# 2_Unextended_Standard_matrix.net
KiCad netlist of a schematic drawn in Altium Designer
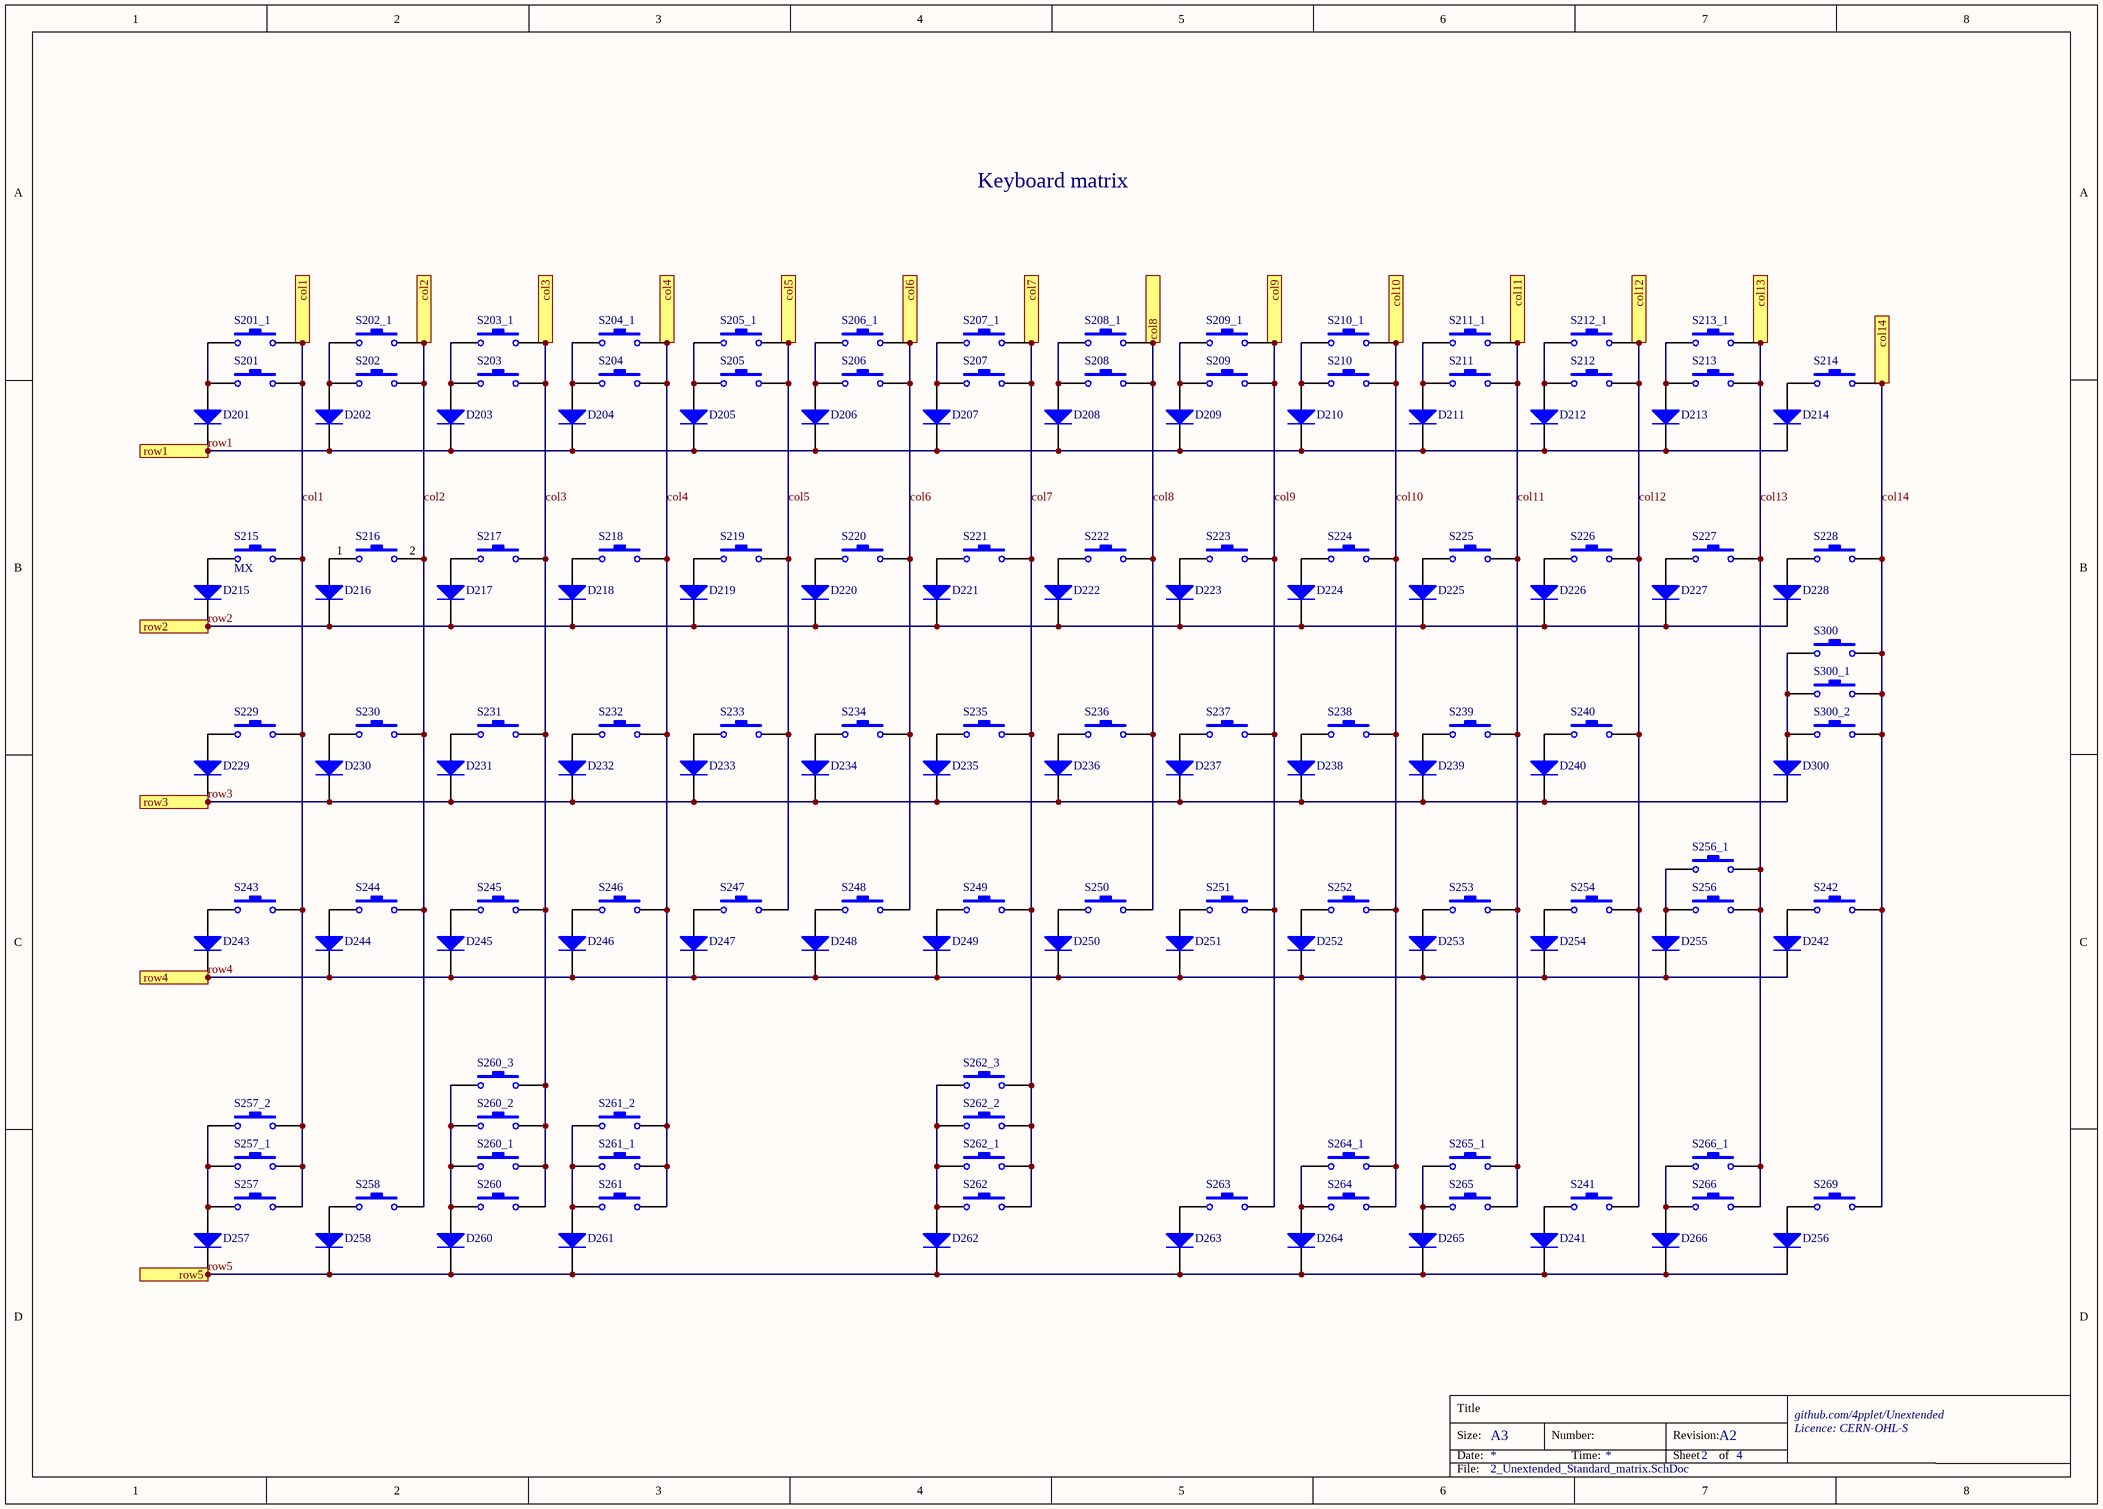
[diagram p0: 2_Unextended_Standard_matrix.SchDoc]

(export (version "E")
  (design (tool "Eeschema 10.0.6"))
  (components
    (comp (ref "D201")
      (value "Diode")
      (footprint "SOD-123")
      (description "Default Diode")
      (fields (field (name "LCSC PART #") "C81598") (field (name "MRF.PART") "1N4148W"))
      (libsource (lib "Miscellaneous Devices") (part "Diode"))
    )
    (comp (ref "D202")
      (value "Diode")
      (footprint "SOD-123")
      (description "Default Diode")
      (fields (field (name "LCSC PART #") "C81598") (field (name "MRF.PART") "1N4148W"))
      (libsource (lib "Miscellaneous Devices") (part "Diode"))
    )
    (comp (ref "D203")
      (value "Diode")
      (footprint "SOD-123")
      (description "Default Diode")
      (fields (field (name "LCSC PART #") "C81598") (field (name "MRF.PART") "1N4148W"))
      (libsource (lib "Miscellaneous Devices") (part "Diode"))
    )
    (comp (ref "D204")
      (value "Diode")
      (footprint "SOD-123")
      (description "Default Diode")
      (fields (field (name "LCSC PART #") "C81598") (field (name "MRF.PART") "1N4148W"))
      (libsource (lib "Miscellaneous Devices") (part "Diode"))
    )
    (comp (ref "D205")
      (value "Diode")
      (footprint "SOD-123")
      (description "Default Diode")
      (fields (field (name "LCSC PART #") "C81598") (field (name "MRF.PART") "1N4148W"))
      (libsource (lib "Miscellaneous Devices") (part "Diode"))
    )
    (comp (ref "D206")
      (value "Diode")
      (footprint "SOD-123")
      (description "Default Diode")
      (fields (field (name "LCSC PART #") "C81598") (field (name "MRF.PART") "1N4148W"))
      (libsource (lib "Miscellaneous Devices") (part "Diode"))
    )
    (comp (ref "D207")
      (value "Diode")
      (footprint "SOD-123")
      (description "Default Diode")
      (fields (field (name "LCSC PART #") "C81598") (field (name "MRF.PART") "1N4148W"))
      (libsource (lib "Miscellaneous Devices") (part "Diode"))
    )
    (comp (ref "D208")
      (value "Diode")
      (footprint "SOD-123")
      (description "Default Diode")
      (fields (field (name "LCSC PART #") "C81598") (field (name "MRF.PART") "1N4148W"))
      (libsource (lib "Miscellaneous Devices") (part "Diode"))
    )
    (comp (ref "D209")
      (value "Diode")
      (footprint "SOD-123")
      (description "Default Diode")
      (fields (field (name "LCSC PART #") "C81598") (field (name "MRF.PART") "1N4148W"))
      (libsource (lib "Miscellaneous Devices") (part "Diode"))
    )
    (comp (ref "D210")
      (value "Diode")
      (footprint "SOD-123")
      (description "Default Diode")
      (fields (field (name "LCSC PART #") "C81598") (field (name "MRF.PART") "1N4148W"))
      (libsource (lib "Miscellaneous Devices") (part "Diode"))
    )
    (comp (ref "D211")
      (value "Diode")
      (footprint "SOD-123")
      (description "Default Diode")
      (fields (field (name "LCSC PART #") "C81598") (field (name "MRF.PART") "1N4148W"))
      (libsource (lib "Miscellaneous Devices") (part "Diode"))
    )
    (comp (ref "D212")
      (value "Diode")
      (footprint "SOD-123")
      (description "Default Diode")
      (fields (field (name "LCSC PART #") "C81598") (field (name "MRF.PART") "1N4148W"))
      (libsource (lib "Miscellaneous Devices") (part "Diode"))
    )
    (comp (ref "D213")
      (value "Diode")
      (footprint "SOD-123")
      (description "Default Diode")
      (fields (field (name "LCSC PART #") "C81598") (field (name "MRF.PART") "1N4148W"))
      (libsource (lib "Miscellaneous Devices") (part "Diode"))
    )
    (comp (ref "D214")
      (value "Diode")
      (footprint "SOD-123")
      (description "Default Diode")
      (fields (field (name "LCSC PART #") "C81598") (field (name "MRF.PART") "1N4148W"))
      (libsource (lib "Miscellaneous Devices") (part "Diode"))
    )
    (comp (ref "D215")
      (value "Diode")
      (footprint "SOD-123")
      (description "Default Diode")
      (fields (field (name "LCSC PART #") "C81598") (field (name "MRF.PART") "1N4148W"))
      (libsource (lib "Miscellaneous Devices") (part "Diode"))
    )
    (comp (ref "D216")
      (value "Diode")
      (footprint "SOD-123")
      (description "Default Diode")
      (fields (field (name "LCSC PART #") "C81598") (field (name "MRF.PART") "1N4148W"))
      (libsource (lib "Miscellaneous Devices") (part "Diode"))
    )
    (comp (ref "D217")
      (value "Diode")
      (footprint "SOD-123")
      (description "Default Diode")
      (fields (field (name "LCSC PART #") "C81598") (field (name "MRF.PART") "1N4148W"))
      (libsource (lib "Miscellaneous Devices") (part "Diode"))
    )
    (comp (ref "D218")
      (value "Diode")
      (footprint "SOD-123")
      (description "Default Diode")
      (fields (field (name "LCSC PART #") "C81598") (field (name "MRF.PART") "1N4148W"))
      (libsource (lib "Miscellaneous Devices") (part "Diode"))
    )
    (comp (ref "D219")
      (value "Diode")
      (footprint "SOD-123")
      (description "Default Diode")
      (fields (field (name "LCSC PART #") "C81598") (field (name "MRF.PART") "1N4148W"))
      (libsource (lib "Miscellaneous Devices") (part "Diode"))
    )
    (comp (ref "D220")
      (value "Diode")
      (footprint "SOD-123")
      (description "Default Diode")
      (fields (field (name "LCSC PART #") "C81598") (field (name "MRF.PART") "1N4148W"))
      (libsource (lib "Miscellaneous Devices") (part "Diode"))
    )
    (comp (ref "D221")
      (value "Diode")
      (footprint "SOD-123")
      (description "Default Diode")
      (fields (field (name "LCSC PART #") "C81598") (field (name "MRF.PART") "1N4148W"))
      (libsource (lib "Miscellaneous Devices") (part "Diode"))
    )
    (comp (ref "D222")
      (value "Diode")
      (footprint "SOD-123")
      (description "Default Diode")
      (fields (field (name "LCSC PART #") "C81598") (field (name "MRF.PART") "1N4148W"))
      (libsource (lib "Miscellaneous Devices") (part "Diode"))
    )
    (comp (ref "D223")
      (value "Diode")
      (footprint "SOD-123")
      (description "Default Diode")
      (fields (field (name "LCSC PART #") "C81598") (field (name "MRF.PART") "1N4148W"))
      (libsource (lib "Miscellaneous Devices") (part "Diode"))
    )
    (comp (ref "D224")
      (value "Diode")
      (footprint "SOD-123")
      (description "Default Diode")
      (fields (field (name "LCSC PART #") "C81598") (field (name "MRF.PART") "1N4148W"))
      (libsource (lib "Miscellaneous Devices") (part "Diode"))
    )
    (comp (ref "D225")
      (value "Diode")
      (footprint "SOD-123")
      (description "Default Diode")
      (fields (field (name "LCSC PART #") "C81598") (field (name "MRF.PART") "1N4148W"))
      (libsource (lib "Miscellaneous Devices") (part "Diode"))
    )
    (comp (ref "D226")
      (value "Diode")
      (footprint "SOD-123")
      (description "Default Diode")
      (fields (field (name "LCSC PART #") "C81598") (field (name "MRF.PART") "1N4148W"))
      (libsource (lib "Miscellaneous Devices") (part "Diode"))
    )
    (comp (ref "D227")
      (value "Diode")
      (footprint "SOD-123")
      (description "Default Diode")
      (fields (field (name "LCSC PART #") "C81598") (field (name "MRF.PART") "1N4148W"))
      (libsource (lib "Miscellaneous Devices") (part "Diode"))
    )
    (comp (ref "D228")
      (value "Diode")
      (footprint "SOD-123")
      (description "Default Diode")
      (fields (field (name "LCSC PART #") "C81598") (field (name "MRF.PART") "1N4148W"))
      (libsource (lib "Miscellaneous Devices") (part "Diode"))
    )
    (comp (ref "D229")
      (value "Diode")
      (footprint "SOD-123")
      (description "Default Diode")
      (fields (field (name "LCSC PART #") "C81598") (field (name "MRF.PART") "1N4148W"))
      (libsource (lib "Miscellaneous Devices") (part "Diode"))
    )
    (comp (ref "D230")
      (value "Diode")
      (footprint "SOD-123")
      (description "Default Diode")
      (fields (field (name "LCSC PART #") "C81598") (field (name "MRF.PART") "1N4148W"))
      (libsource (lib "Miscellaneous Devices") (part "Diode"))
    )
    (comp (ref "D231")
      (value "Diode")
      (footprint "SOD-123")
      (description "Default Diode")
      (fields (field (name "LCSC PART #") "C81598") (field (name "MRF.PART") "1N4148W"))
      (libsource (lib "Miscellaneous Devices") (part "Diode"))
    )
    (comp (ref "D232")
      (value "Diode")
      (footprint "SOD-123")
      (description "Default Diode")
      (fields (field (name "LCSC PART #") "C81598") (field (name "MRF.PART") "1N4148W"))
      (libsource (lib "Miscellaneous Devices") (part "Diode"))
    )
    (comp (ref "D233")
      (value "Diode")
      (footprint "SOD-123")
      (description "Default Diode")
      (fields (field (name "LCSC PART #") "C81598") (field (name "MRF.PART") "1N4148W"))
      (libsource (lib "Miscellaneous Devices") (part "Diode"))
    )
    (comp (ref "D234")
      (value "Diode")
      (footprint "SOD-123")
      (description "Default Diode")
      (fields (field (name "LCSC PART #") "C81598") (field (name "MRF.PART") "1N4148W"))
      (libsource (lib "Miscellaneous Devices") (part "Diode"))
    )
    (comp (ref "D235")
      (value "Diode")
      (footprint "SOD-123")
      (description "Default Diode")
      (fields (field (name "LCSC PART #") "C81598") (field (name "MRF.PART") "1N4148W"))
      (libsource (lib "Miscellaneous Devices") (part "Diode"))
    )
    (comp (ref "D236")
      (value "Diode")
      (footprint "SOD-123")
      (description "Default Diode")
      (fields (field (name "LCSC PART #") "C81598") (field (name "MRF.PART") "1N4148W"))
      (libsource (lib "Miscellaneous Devices") (part "Diode"))
    )
    (comp (ref "D237")
      (value "Diode")
      (footprint "SOD-123")
      (description "Default Diode")
      (fields (field (name "LCSC PART #") "C81598") (field (name "MRF.PART") "1N4148W"))
      (libsource (lib "Miscellaneous Devices") (part "Diode"))
    )
    (comp (ref "D238")
      (value "Diode")
      (footprint "SOD-123")
      (description "Default Diode")
      (fields (field (name "LCSC PART #") "C81598") (field (name "MRF.PART") "1N4148W"))
      (libsource (lib "Miscellaneous Devices") (part "Diode"))
    )
    (comp (ref "D239")
      (value "Diode")
      (footprint "SOD-123")
      (description "Default Diode")
      (fields (field (name "LCSC PART #") "C81598") (field (name "MRF.PART") "1N4148W"))
      (libsource (lib "Miscellaneous Devices") (part "Diode"))
    )
    (comp (ref "D240")
      (value "Diode")
      (footprint "SOD-123")
      (description "Default Diode")
      (fields (field (name "LCSC PART #") "C81598") (field (name "MRF.PART") "1N4148W"))
      (libsource (lib "Miscellaneous Devices") (part "Diode"))
    )
    (comp (ref "D241")
      (value "Diode")
      (footprint "SOD-123")
      (description "Default Diode")
      (fields (field (name "LCSC PART #") "C81598") (field (name "MRF.PART") "1N4148W"))
      (libsource (lib "Miscellaneous Devices") (part "Diode"))
    )
    (comp (ref "D242")
      (value "Diode")
      (footprint "SOD-123")
      (description "Default Diode")
      (fields (field (name "LCSC PART #") "C81598") (field (name "MRF.PART") "1N4148W"))
      (libsource (lib "Miscellaneous Devices") (part "Diode"))
    )
    (comp (ref "D243")
      (value "Diode")
      (footprint "SOD-123")
      (description "Default Diode")
      (fields (field (name "LCSC PART #") "C81598") (field (name "MRF.PART") "1N4148W"))
      (libsource (lib "Miscellaneous Devices") (part "Diode"))
    )
    (comp (ref "D244")
      (value "Diode")
      (footprint "SOD-123")
      (description "Default Diode")
      (fields (field (name "LCSC PART #") "C81598") (field (name "MRF.PART") "1N4148W"))
      (libsource (lib "Miscellaneous Devices") (part "Diode"))
    )
    (comp (ref "D245")
      (value "Diode")
      (footprint "SOD-123")
      (description "Default Diode")
      (fields (field (name "LCSC PART #") "C81598") (field (name "MRF.PART") "1N4148W"))
      (libsource (lib "Miscellaneous Devices") (part "Diode"))
    )
    (comp (ref "D246")
      (value "Diode")
      (footprint "SOD-123")
      (description "Default Diode")
      (fields (field (name "LCSC PART #") "C81598") (field (name "MRF.PART") "1N4148W"))
      (libsource (lib "Miscellaneous Devices") (part "Diode"))
    )
    (comp (ref "D247")
      (value "Diode")
      (footprint "SOD-123")
      (description "Default Diode")
      (fields (field (name "LCSC PART #") "C81598") (field (name "MRF.PART") "1N4148W"))
      (libsource (lib "Miscellaneous Devices") (part "Diode"))
    )
    (comp (ref "D248")
      (value "Diode")
      (footprint "SOD-123")
      (description "Default Diode")
      (fields (field (name "LCSC PART #") "C81598") (field (name "MRF.PART") "1N4148W"))
      (libsource (lib "Miscellaneous Devices") (part "Diode"))
    )
    (comp (ref "D249")
      (value "Diode")
      (footprint "SOD-123")
      (description "Default Diode")
      (fields (field (name "LCSC PART #") "C81598") (field (name "MRF.PART") "1N4148W"))
      (libsource (lib "Miscellaneous Devices") (part "Diode"))
    )
    (comp (ref "D250")
      (value "Diode")
      (footprint "SOD-123")
      (description "Default Diode")
      (fields (field (name "LCSC PART #") "C81598") (field (name "MRF.PART") "1N4148W"))
      (libsource (lib "Miscellaneous Devices") (part "Diode"))
    )
    (comp (ref "D251")
      (value "Diode")
      (footprint "SOD-123")
      (description "Default Diode")
      (fields (field (name "LCSC PART #") "C81598") (field (name "MRF.PART") "1N4148W"))
      (libsource (lib "Miscellaneous Devices") (part "Diode"))
    )
    (comp (ref "D252")
      (value "Diode")
      (footprint "SOD-123")
      (description "Default Diode")
      (fields (field (name "LCSC PART #") "C81598") (field (name "MRF.PART") "1N4148W"))
      (libsource (lib "Miscellaneous Devices") (part "Diode"))
    )
    (comp (ref "D253")
      (value "Diode")
      (footprint "SOD-123")
      (description "Default Diode")
      (fields (field (name "LCSC PART #") "C81598") (field (name "MRF.PART") "1N4148W"))
      (libsource (lib "Miscellaneous Devices") (part "Diode"))
    )
    (comp (ref "D254")
      (value "Diode")
      (footprint "SOD-123")
      (description "Default Diode")
      (fields (field (name "LCSC PART #") "C81598") (field (name "MRF.PART") "1N4148W"))
      (libsource (lib "Miscellaneous Devices") (part "Diode"))
    )
    (comp (ref "D255")
      (value "Diode")
      (footprint "SOD-123")
      (description "Default Diode")
      (fields (field (name "LCSC PART #") "C81598") (field (name "MRF.PART") "1N4148W"))
      (libsource (lib "Miscellaneous Devices") (part "Diode"))
    )
    (comp (ref "D256")
      (value "Diode")
      (footprint "SOD-123")
      (description "Default Diode")
      (fields (field (name "LCSC PART #") "C81598") (field (name "MRF.PART") "1N4148W"))
      (libsource (lib "Miscellaneous Devices") (part "Diode"))
    )
    (comp (ref "D257")
      (value "Diode")
      (footprint "SOD-123")
      (description "Default Diode")
      (fields (field (name "LCSC PART #") "C81598") (field (name "MRF.PART") "1N4148W"))
      (libsource (lib "Miscellaneous Devices") (part "Diode"))
    )
    (comp (ref "D258")
      (value "Diode")
      (footprint "SOD-123")
      (description "Default Diode")
      (fields (field (name "LCSC PART #") "C81598") (field (name "MRF.PART") "1N4148W"))
      (libsource (lib "Miscellaneous Devices") (part "Diode"))
    )
    (comp (ref "D260")
      (value "Diode")
      (footprint "SOD-123")
      (description "Default Diode")
      (fields (field (name "LCSC PART #") "C81598") (field (name "MRF.PART") "1N4148W"))
      (libsource (lib "Miscellaneous Devices") (part "Diode"))
    )
    (comp (ref "D261")
      (value "Diode")
      (footprint "SOD-123")
      (description "Default Diode")
      (fields (field (name "LCSC PART #") "C81598") (field (name "MRF.PART") "1N4148W"))
      (libsource (lib "Miscellaneous Devices") (part "Diode"))
    )
    (comp (ref "D262")
      (value "Diode")
      (footprint "SOD-123")
      (description "Default Diode")
      (fields (field (name "LCSC PART #") "C81598") (field (name "MRF.PART") "1N4148W"))
      (libsource (lib "Miscellaneous Devices") (part "Diode"))
    )
    (comp (ref "D263")
      (value "Diode")
      (footprint "SOD-123")
      (description "Default Diode")
      (fields (field (name "LCSC PART #") "C81598") (field (name "MRF.PART") "1N4148W"))
      (libsource (lib "Miscellaneous Devices") (part "Diode"))
    )
    (comp (ref "D264")
      (value "Diode")
      (footprint "SOD-123")
      (description "Default Diode")
      (fields (field (name "LCSC PART #") "C81598") (field (name "MRF.PART") "1N4148W"))
      (libsource (lib "Miscellaneous Devices") (part "Diode"))
    )
    (comp (ref "D265")
      (value "Diode")
      (footprint "SOD-123")
      (description "Default Diode")
      (fields (field (name "LCSC PART #") "C81598") (field (name "MRF.PART") "1N4148W"))
      (libsource (lib "Miscellaneous Devices") (part "Diode"))
    )
    (comp (ref "D266")
      (value "Diode")
      (footprint "SOD-123")
      (description "Default Diode")
      (fields (field (name "LCSC PART #") "C81598") (field (name "MRF.PART") "1N4148W"))
      (libsource (lib "Miscellaneous Devices") (part "Diode"))
    )
    (comp (ref "D300")
      (value "Diode")
      (footprint "SOD-123")
      (description "Default Diode")
      (fields (field (name "LCSC PART #") "C81598") (field (name "MRF.PART") "1N4148W"))
      (libsource (lib "Miscellaneous Devices") (part "Diode"))
    )
    (comp (ref "S201")
      (value "ALPS")
      (footprint "Alps-switch - switched pol")
      (description "Switch")
      (libsource (lib "Miscellaneous Devices") (part "SW-PB"))
    )
    (comp (ref "S201_1")
      (value "ALPS")
      (footprint "Alps-switch")
      (description "Switch")
      (libsource (lib "Miscellaneous Devices") (part "SW-PB"))
    )
    (comp (ref "S202")
      (value "ALPS")
      (footprint "Alps-switch - switched pol")
      (description "Switch")
      (libsource (lib "Miscellaneous Devices") (part "SW-PB"))
    )
    (comp (ref "S202_1")
      (value "ALPS")
      (footprint "Alps-switch")
      (description "Switch")
      (libsource (lib "Miscellaneous Devices") (part "SW-PB"))
    )
    (comp (ref "S203")
      (value "ALPS")
      (footprint "Alps-switch - switched pol")
      (description "Switch")
      (libsource (lib "Miscellaneous Devices") (part "SW-PB"))
    )
    (comp (ref "S203_1")
      (value "ALPS")
      (footprint "Alps-switch")
      (description "Switch")
      (libsource (lib "Miscellaneous Devices") (part "SW-PB"))
    )
    (comp (ref "S204")
      (value "ALPS")
      (footprint "Alps-switch - switched pol")
      (description "Switch")
      (libsource (lib "Miscellaneous Devices") (part "SW-PB"))
    )
    (comp (ref "S204_1")
      (value "ALPS")
      (footprint "Alps-switch")
      (description "Switch")
      (libsource (lib "Miscellaneous Devices") (part "SW-PB"))
    )
    (comp (ref "S205")
      (value "ALPS")
      (footprint "Alps-switch - switched pol")
      (description "Switch")
      (libsource (lib "Miscellaneous Devices") (part "SW-PB"))
    )
    (comp (ref "S205_1")
      (value "ALPS")
      (footprint "Alps-switch")
      (description "Switch")
      (libsource (lib "Miscellaneous Devices") (part "SW-PB"))
    )
    (comp (ref "S206")
      (value "ALPS")
      (footprint "Alps-switch - switched pol")
      (description "Switch")
      (libsource (lib "Miscellaneous Devices") (part "SW-PB"))
    )
    (comp (ref "S206_1")
      (value "ALPS")
      (footprint "Alps-switch")
      (description "Switch")
      (libsource (lib "Miscellaneous Devices") (part "SW-PB"))
    )
    (comp (ref "S207")
      (value "ALPS")
      (footprint "Alps-switch - switched pol")
      (description "Switch")
      (libsource (lib "Miscellaneous Devices") (part "SW-PB"))
    )
    (comp (ref "S207_1")
      (value "ALPS")
      (footprint "Alps-switch")
      (description "Switch")
      (libsource (lib "Miscellaneous Devices") (part "SW-PB"))
    )
    (comp (ref "S208")
      (value "ALPS")
      (footprint "Alps-switch - switched pol")
      (description "Switch")
      (libsource (lib "Miscellaneous Devices") (part "SW-PB"))
    )
    (comp (ref "S208_1")
      (value "ALPS")
      (footprint "Alps-switch")
      (description "Switch")
      (libsource (lib "Miscellaneous Devices") (part "SW-PB"))
    )
    (comp (ref "S209")
      (value "ALPS")
      (footprint "Alps-switch - switched pol")
      (description "Switch")
      (libsource (lib "Miscellaneous Devices") (part "SW-PB"))
    )
    (comp (ref "S209_1")
      (value "ALPS")
      (footprint "Alps-switch")
      (description "Switch")
      (libsource (lib "Miscellaneous Devices") (part "SW-PB"))
    )
    (comp (ref "S210")
      (value "ALPS")
      (footprint "Alps-switch - switched pol")
      (description "Switch")
      (libsource (lib "Miscellaneous Devices") (part "SW-PB"))
    )
    (comp (ref "S210_1")
      (value "ALPS")
      (footprint "Alps-switch")
      (description "Switch")
      (libsource (lib "Miscellaneous Devices") (part "SW-PB"))
    )
    (comp (ref "S211")
      (value "ALPS")
      (footprint "Alps-switch - switched pol")
      (description "Switch")
      (libsource (lib "Miscellaneous Devices") (part "SW-PB"))
    )
    (comp (ref "S211_1")
      (value "ALPS")
      (footprint "Alps-switch")
      (description "Switch")
      (libsource (lib "Miscellaneous Devices") (part "SW-PB"))
    )
    (comp (ref "S212")
      (value "ALPS")
      (footprint "Alps-switch - switched pol")
      (description "Switch")
      (libsource (lib "Miscellaneous Devices") (part "SW-PB"))
    )
    (comp (ref "S212_1")
      (value "ALPS")
      (footprint "Alps-switch")
      (description "Switch")
      (libsource (lib "Miscellaneous Devices") (part "SW-PB"))
    )
    (comp (ref "S213")
      (value "ALPS")
      (footprint "Alps-switch - switched pol")
      (description "Switch")
      (libsource (lib "Miscellaneous Devices") (part "SW-PB"))
    )
    (comp (ref "S213_1")
      (value "ALPS")
      (footprint "Alps-switch")
      (description "Switch")
      (libsource (lib "Miscellaneous Devices") (part "SW-PB"))
    )
    (comp (ref "S214")
      (value "ALPS")
      (footprint "ALPS-switch - 1.5U")
      (description "Switch")
      (libsource (lib "Miscellaneous Devices") (part "SW-PB"))
    )
    (comp (ref "S215")
      (value "MX")
      (footprint "Alps-switch - switched pol")
      (description "TAB")
      (libsource (lib "Miscellaneous Devices") (part "SW-PB"))
    )
    (comp (ref "S216")
      (value "ALPS")
      (footprint "Alps-switch")
      (description "Switch")
      (libsource (lib "") (part "SW-PB_1"))
    )
    (comp (ref "S217")
      (value "ALPS")
      (footprint "Alps-switch - switched pol")
      (description "Switch")
      (libsource (lib "Miscellaneous Devices") (part "SW-PB"))
    )
    (comp (ref "S218")
      (value "ALPS")
      (footprint "Alps-switch - switched pol")
      (description "Switch")
      (libsource (lib "Miscellaneous Devices") (part "SW-PB"))
    )
    (comp (ref "S219")
      (value "ALPS")
      (footprint "Alps-switch - switched pol")
      (description "Switch")
      (libsource (lib "Miscellaneous Devices") (part "SW-PB"))
    )
    (comp (ref "S220")
      (value "ALPS")
      (footprint "Alps-switch - switched pol")
      (description "Switch")
      (libsource (lib "Miscellaneous Devices") (part "SW-PB"))
    )
    (comp (ref "S221")
      (value "ALPS")
      (footprint "Alps-switch - switched pol")
      (description "Switch")
      (libsource (lib "Miscellaneous Devices") (part "SW-PB"))
    )
    (comp (ref "S222")
      (value "ALPS")
      (footprint "Alps-switch - switched pol")
      (description "Switch")
      (libsource (lib "Miscellaneous Devices") (part "SW-PB"))
    )
    (comp (ref "S223")
      (value "ALPS")
      (footprint "Alps-switch - switched pol")
      (description "Switch")
      (libsource (lib "Miscellaneous Devices") (part "SW-PB"))
    )
    (comp (ref "S224")
      (value "ALPS")
      (footprint "Alps-switch - switched pol")
      (description "Switch")
      (libsource (lib "Miscellaneous Devices") (part "SW-PB"))
    )
    (comp (ref "S225")
      (value "ALPS")
      (footprint "Alps-switch - switched pol")
      (description "Switch")
      (libsource (lib "Miscellaneous Devices") (part "SW-PB"))
    )
    (comp (ref "S226")
      (value "ALPS")
      (footprint "Alps-switch")
      (description "Switch")
      (libsource (lib "Miscellaneous Devices") (part "SW-PB"))
    )
    (comp (ref "S227")
      (value "ALPS")
      (footprint "Alps-switch")
      (description "Switch")
      (libsource (lib "Miscellaneous Devices") (part "SW-PB"))
    )
    (comp (ref "S228")
      (value "ALPS")
      (footprint "Alps-switch - switched pol")
      (description "Switch")
      (libsource (lib "Miscellaneous Devices") (part "SW-PB"))
    )
    (comp (ref "S229")
      (value "ALPS")
      (footprint "Alps-switch - switched pol")
      (description "Switch")
      (libsource (lib "Miscellaneous Devices") (part "SW-PB"))
    )
    (comp (ref "S230")
      (value "ALPS")
      (footprint "Alps-switch")
      (description "Switch")
      (libsource (lib "Miscellaneous Devices") (part "SW-PB"))
    )
    (comp (ref "S231")
      (value "ALPS")
      (footprint "Alps-switch - switched pol")
      (description "Switch")
      (libsource (lib "Miscellaneous Devices") (part "SW-PB"))
    )
    (comp (ref "S232")
      (value "ALPS")
      (footprint "Alps-switch - switched pol")
      (description "Switch")
      (libsource (lib "Miscellaneous Devices") (part "SW-PB"))
    )
    (comp (ref "S233")
      (value "ALPS")
      (footprint "Alps-switch - switched pol")
      (description "Switch")
      (libsource (lib "Miscellaneous Devices") (part "SW-PB"))
    )
    (comp (ref "S234")
      (value "ALPS")
      (footprint "Alps-switch - switched pol")
      (description "Switch")
      (libsource (lib "Miscellaneous Devices") (part "SW-PB"))
    )
    (comp (ref "S235")
      (value "ALPS")
      (footprint "Alps-switch - switched pol")
      (description "Switch")
      (libsource (lib "Miscellaneous Devices") (part "SW-PB"))
    )
    (comp (ref "S236")
      (value "ALPS")
      (footprint "Alps-switch - switched pol")
      (description "Switch")
      (libsource (lib "Miscellaneous Devices") (part "SW-PB"))
    )
    (comp (ref "S237")
      (value "ALPS")
      (footprint "Alps-switch - switched pol")
      (description "Switch")
      (libsource (lib "Miscellaneous Devices") (part "SW-PB"))
    )
    (comp (ref "S238")
      (value "ALPS")
      (footprint "Alps-switch - switched pol")
      (description "Switch")
      (libsource (lib "Miscellaneous Devices") (part "SW-PB"))
    )
    (comp (ref "S239")
      (value "ALPS")
      (footprint "Alps-switch - switched pol")
      (description "Switch")
      (libsource (lib "Miscellaneous Devices") (part "SW-PB"))
    )
    (comp (ref "S240")
      (value "ALPS")
      (footprint "Alps-switch - switched pol")
      (description "Switch")
      (libsource (lib "Miscellaneous Devices") (part "SW-PB"))
    )
    (comp (ref "S241")
      (value "ALPS")
      (footprint "Alps-switch")
      (description "Switch")
      (libsource (lib "Miscellaneous Devices") (part "SW-PB"))
    )
    (comp (ref "S242")
      (value "ALPS")
      (footprint "Alps-switch")
      (description "Switch")
      (libsource (lib "Miscellaneous Devices") (part "SW-PB"))
    )
    (comp (ref "S243")
      (value "ALPS")
      (footprint "ALPS-switch - Left shift v2")
      (description "Switch")
      (libsource (lib "Miscellaneous Devices") (part "SW-PB"))
    )
    (comp (ref "S244")
      (value "ALPS")
      (footprint "Alps-switch")
      (description "Switch")
      (libsource (lib "Miscellaneous Devices") (part "SW-PB"))
    )
    (comp (ref "S245")
      (value "ALPS")
      (footprint "Alps-switch - switched pol")
      (description "Switch")
      (libsource (lib "Miscellaneous Devices") (part "SW-PB"))
    )
    (comp (ref "S246")
      (value "ALPS")
      (footprint "Alps-switch - switched pol")
      (description "Switch")
      (libsource (lib "Miscellaneous Devices") (part "SW-PB"))
    )
    (comp (ref "S247")
      (value "ALPS")
      (footprint "Alps-switch - switched pol")
      (description "Switch")
      (libsource (lib "Miscellaneous Devices") (part "SW-PB"))
    )
    (comp (ref "S248")
      (value "ALPS")
      (footprint "Alps-switch - switched pol")
      (description "Switch")
      (libsource (lib "Miscellaneous Devices") (part "SW-PB"))
    )
    (comp (ref "S249")
      (value "ALPS")
      (footprint "Alps-switch - switched pol")
      (description "Switch")
      (libsource (lib "Miscellaneous Devices") (part "SW-PB"))
    )
    (comp (ref "S250")
      (value "ALPS")
      (footprint "Alps-switch - switched pol")
      (description "Switch")
      (libsource (lib "Miscellaneous Devices") (part "SW-PB"))
    )
    (comp (ref "S251")
      (value "ALPS")
      (footprint "Alps-switch - switched pol")
      (description "Switch")
      (libsource (lib "Miscellaneous Devices") (part "SW-PB"))
    )
    (comp (ref "S252")
      (value "ALPS")
      (footprint "Alps-switch - switched pol")
      (description "Switch")
      (libsource (lib "Miscellaneous Devices") (part "SW-PB"))
    )
    (comp (ref "S253")
      (value "ALPS")
      (footprint "Alps-switch - switched pol")
      (description "Switch")
      (libsource (lib "Miscellaneous Devices") (part "SW-PB"))
    )
    (comp (ref "S254")
      (value "ALPS")
      (footprint "Alps-switch - switched pol")
      (description "Switch")
      (libsource (lib "Miscellaneous Devices") (part "SW-PB"))
    )
    (comp (ref "S256")
      (value "ALPS")
      (footprint "ALPS-switch - 2.25U")
      (description "Switch")
      (libsource (lib "Miscellaneous Devices") (part "SW-PB"))
    )
    (comp (ref "S256_1")
      (value "ALPS")
      (footprint "Alps-switch - switched pol")
      (description "Switch")
      (libsource (lib "Miscellaneous Devices") (part "SW-PB"))
    )
    (comp (ref "S257")
      (value "ALPS")
      (footprint "Alps-switch - switched pol")
      (description "Switch")
      (libsource (lib "Miscellaneous Devices") (part "SW-PB"))
    )
    (comp (ref "S257_1")
      (value "ALPS")
      (footprint "Alps-switch")
      (description "Switch")
      (libsource (lib "Miscellaneous Devices") (part "SW-PB"))
    )
    (comp (ref "S257_2")
      (value "ALPS")
      (footprint "Alps-switch")
      (description "Switch")
      (libsource (lib "Miscellaneous Devices") (part "SW-PB"))
    )
    (comp (ref "S258")
      (value "ALPS")
      (footprint "Alps-switch")
      (description "Switch")
      (libsource (lib "Miscellaneous Devices") (part "SW-PB"))
    )
    (comp (ref "S260")
      (value "ALPS")
      (footprint "Alps-switch")
      (description "Switch")
      (libsource (lib "Miscellaneous Devices") (part "SW-PB"))
    )
    (comp (ref "S260_1")
      (value "ALPS")
      (footprint "Alps-switch - switched pol")
      (description "Switch")
      (libsource (lib "Miscellaneous Devices") (part "SW-PB"))
    )
    (comp (ref "S260_2")
      (value "ALPS")
      (footprint "Alps-switch")
      (description "Switch")
      (libsource (lib "Miscellaneous Devices") (part "SW-PB"))
    )
    (comp (ref "S260_3")
      (value "ALPS")
      (footprint "Alps-switch - switched pol")
      (description "Switch")
      (libsource (lib "Miscellaneous Devices") (part "SW-PB"))
    )
    (comp (ref "S261")
      (value "ALPS")
      (footprint "Alps-switch")
      (description "Switch")
      (libsource (lib "Miscellaneous Devices") (part "SW-PB"))
    )
    (comp (ref "S261_1")
      (value "ALPS")
      (footprint "Alps-switch - switched pol")
      (description "Switch")
      (libsource (lib "Miscellaneous Devices") (part "SW-PB"))
    )
    (comp (ref "S261_2")
      (value "ALPS")
      (footprint "Alps-switch - switched pol")
      (description "Switch")
      (libsource (lib "Miscellaneous Devices") (part "SW-PB"))
    )
    (comp (ref "S262")
      (value "ALPS")
      (footprint "Alps-switch")
      (description "Switch")
      (libsource (lib "Miscellaneous Devices") (part "SW-PB"))
    )
    (comp (ref "S262_1")
      (value "ALPS")
      (footprint "Alps-switch")
      (description "Switch")
      (libsource (lib "Miscellaneous Devices") (part "SW-PB"))
    )
    (comp (ref "S262_2")
      (value "ALPS")
      (footprint "Alps-switch - switched pol")
      (description "Switch")
      (libsource (lib "Miscellaneous Devices") (part "SW-PB"))
    )
    (comp (ref "S262_3")
      (value "ALPS")
      (footprint "Alps-switch")
      (description "Switch")
      (libsource (lib "Miscellaneous Devices") (part "SW-PB"))
    )
    (comp (ref "S263")
      (value "ALPS")
      (footprint "Alps-switch")
      (description "Switch")
      (libsource (lib "Miscellaneous Devices") (part "SW-PB"))
    )
    (comp (ref "S264")
      (value "ALPS")
      (footprint "Alps-switch - switched pol")
      (description "Switch")
      (libsource (lib "Miscellaneous Devices") (part "SW-PB"))
    )
    (comp (ref "S264_1")
      (value "ALPS")
      (footprint "Alps-switch")
      (description "Switch")
      (libsource (lib "Miscellaneous Devices") (part "SW-PB"))
    )
    (comp (ref "S265")
      (value "ALPS")
      (footprint "Alps-switch - switched pol")
      (description "Switch")
      (libsource (lib "Miscellaneous Devices") (part "SW-PB"))
    )
    (comp (ref "S265_1")
      (value "ALPS")
      (footprint "Alps-switch")
      (description "Switch")
      (libsource (lib "Miscellaneous Devices") (part "SW-PB"))
    )
    (comp (ref "S266")
      (value "ALPS")
      (footprint "Alps-switch - switched pol")
      (description "Switch")
      (libsource (lib "Miscellaneous Devices") (part "SW-PB"))
    )
    (comp (ref "S266_1")
      (value "ALPS")
      (footprint "Alps-switch")
      (description "Switch")
      (libsource (lib "Miscellaneous Devices") (part "SW-PB"))
    )
    (comp (ref "S269")
      (value "ALPS")
      (footprint "Alps-switch")
      (description "Switch")
      (libsource (lib "Miscellaneous Devices") (part "SW-PB"))
    )
    (comp (ref "S300")
      (value "ALPS")
      (footprint "Alps-switch")
      (description "Switch")
      (libsource (lib "Miscellaneous Devices") (part "SW-PB"))
    )
    (comp (ref "S300_1")
      (value "ALPS")
      (footprint "Alps-switch")
      (description "Switch")
      (libsource (lib "Miscellaneous Devices") (part "SW-PB"))
    )
    (comp (ref "S300_2")
      (value "ALPS")
      (footprint "Alps-switch - switched pol")
      (description "Switch")
      (libsource (lib "Miscellaneous Devices") (part "SW-PB"))
    )
  )
  (nets
    (net (code "1") (name "/col1") (class "Default")
      (node (ref "S201") (pin "2") (pinfunction "2_2") (pintype "passive"))
      (node (ref "S201_1") (pin "2") (pinfunction "2_2") (pintype "passive"))
      (node (ref "S215") (pin "2") (pinfunction "2_2") (pintype "passive"))
      (node (ref "S229") (pin "2") (pinfunction "2_2") (pintype "passive"))
      (node (ref "S243") (pin "2") (pinfunction "2_2") (pintype "passive"))
      (node (ref "S257") (pin "1") (pinfunction "1_1") (pintype "passive"))
      (node (ref "S257_1") (pin "1") (pinfunction "1_1") (pintype "passive"))
      (node (ref "S257_2") (pin "1") (pinfunction "1_1") (pintype "passive"))
    )
    (net (code "2") (name "/col2") (class "Default")
      (node (ref "S202") (pin "2") (pinfunction "2_2") (pintype "passive"))
      (node (ref "S202_1") (pin "2") (pinfunction "2_2") (pintype "passive"))
      (node (ref "S216") (pin "2") (pinfunction "2_2") (pintype "passive"))
      (node (ref "S230") (pin "2") (pinfunction "2_2") (pintype "passive"))
      (node (ref "S244") (pin "1") (pinfunction "1_1") (pintype "passive"))
      (node (ref "S258") (pin "2") (pinfunction "2_2") (pintype "passive"))
    )
    (net (code "3") (name "/col3") (class "Default")
      (node (ref "S203") (pin "2") (pinfunction "2_2") (pintype "passive"))
      (node (ref "S203_1") (pin "2") (pinfunction "2_2") (pintype "passive"))
      (node (ref "S217") (pin "2") (pinfunction "2_2") (pintype "passive"))
      (node (ref "S231") (pin "2") (pinfunction "2_2") (pintype "passive"))
      (node (ref "S245") (pin "2") (pinfunction "2_2") (pintype "passive"))
      (node (ref "S260") (pin "2") (pinfunction "2_2") (pintype "passive"))
      (node (ref "S260_1") (pin "2") (pinfunction "2_2") (pintype "passive"))
      (node (ref "S260_2") (pin "2") (pinfunction "2_2") (pintype "passive"))
      (node (ref "S260_3") (pin "2") (pinfunction "2_2") (pintype "passive"))
    )
    (net (code "4") (name "/col4") (class "Default")
      (node (ref "S204") (pin "2") (pinfunction "2_2") (pintype "passive"))
      (node (ref "S204_1") (pin "2") (pinfunction "2_2") (pintype "passive"))
      (node (ref "S218") (pin "2") (pinfunction "2_2") (pintype "passive"))
      (node (ref "S232") (pin "2") (pinfunction "2_2") (pintype "passive"))
      (node (ref "S246") (pin "2") (pinfunction "2_2") (pintype "passive"))
      (node (ref "S261") (pin "2") (pinfunction "2_2") (pintype "passive"))
      (node (ref "S261_1") (pin "2") (pinfunction "2_2") (pintype "passive"))
      (node (ref "S261_2") (pin "2") (pinfunction "2_2") (pintype "passive"))
    )
    (net (code "5") (name "/col5") (class "Default")
      (node (ref "S205") (pin "2") (pinfunction "2_2") (pintype "passive"))
      (node (ref "S205_1") (pin "2") (pinfunction "2_2") (pintype "passive"))
      (node (ref "S219") (pin "2") (pinfunction "2_2") (pintype "passive"))
      (node (ref "S233") (pin "2") (pinfunction "2_2") (pintype "passive"))
      (node (ref "S247") (pin "2") (pinfunction "2_2") (pintype "passive"))
    )
    (net (code "6") (name "/col6") (class "Default")
      (node (ref "S206") (pin "2") (pinfunction "2_2") (pintype "passive"))
      (node (ref "S206_1") (pin "2") (pinfunction "2_2") (pintype "passive"))
      (node (ref "S220") (pin "2") (pinfunction "2_2") (pintype "passive"))
      (node (ref "S234") (pin "2") (pinfunction "2_2") (pintype "passive"))
      (node (ref "S248") (pin "2") (pinfunction "2_2") (pintype "passive"))
    )
    (net (code "7") (name "/col7") (class "Default")
      (node (ref "S207") (pin "2") (pinfunction "2_2") (pintype "passive"))
      (node (ref "S207_1") (pin "2") (pinfunction "2_2") (pintype "passive"))
      (node (ref "S221") (pin "2") (pinfunction "2_2") (pintype "passive"))
      (node (ref "S235") (pin "2") (pinfunction "2_2") (pintype "passive"))
      (node (ref "S249") (pin "2") (pinfunction "2_2") (pintype "passive"))
      (node (ref "S262") (pin "1") (pinfunction "1_1") (pintype "passive"))
      (node (ref "S262_1") (pin "1") (pinfunction "1_1") (pintype "passive"))
      (node (ref "S262_2") (pin "1") (pinfunction "1_1") (pintype "passive"))
      (node (ref "S262_3") (pin "1") (pinfunction "1_1") (pintype "passive"))
    )
    (net (code "8") (name "/col8") (class "Default")
      (node (ref "S208") (pin "2") (pinfunction "2_2") (pintype "passive"))
      (node (ref "S208_1") (pin "2") (pinfunction "2_2") (pintype "passive"))
      (node (ref "S222") (pin "2") (pinfunction "2_2") (pintype "passive"))
      (node (ref "S236") (pin "2") (pinfunction "2_2") (pintype "passive"))
      (node (ref "S250") (pin "2") (pinfunction "2_2") (pintype "passive"))
    )
    (net (code "9") (name "/col9") (class "Default")
      (node (ref "S209") (pin "2") (pinfunction "2_2") (pintype "passive"))
      (node (ref "S209_1") (pin "2") (pinfunction "2_2") (pintype "passive"))
      (node (ref "S223") (pin "2") (pinfunction "2_2") (pintype "passive"))
      (node (ref "S237") (pin "2") (pinfunction "2_2") (pintype "passive"))
      (node (ref "S251") (pin "2") (pinfunction "2_2") (pintype "passive"))
      (node (ref "S263") (pin "1") (pinfunction "1_1") (pintype "passive"))
    )
    (net (code "10") (name "/col10") (class "Default")
      (node (ref "S210") (pin "2") (pinfunction "2_2") (pintype "passive"))
      (node (ref "S210_1") (pin "2") (pinfunction "2_2") (pintype "passive"))
      (node (ref "S224") (pin "2") (pinfunction "2_2") (pintype "passive"))
      (node (ref "S238") (pin "2") (pinfunction "2_2") (pintype "passive"))
      (node (ref "S252") (pin "2") (pinfunction "2_2") (pintype "passive"))
      (node (ref "S264") (pin "2") (pinfunction "2_2") (pintype "passive"))
      (node (ref "S264_1") (pin "2") (pinfunction "2_2") (pintype "passive"))
    )
    (net (code "11") (name "/col11") (class "Default")
      (node (ref "S211") (pin "2") (pinfunction "2_2") (pintype "passive"))
      (node (ref "S211_1") (pin "2") (pinfunction "2_2") (pintype "passive"))
      (node (ref "S225") (pin "2") (pinfunction "2_2") (pintype "passive"))
      (node (ref "S239") (pin "2") (pinfunction "2_2") (pintype "passive"))
      (node (ref "S253") (pin "2") (pinfunction "2_2") (pintype "passive"))
      (node (ref "S265") (pin "1") (pinfunction "1_1") (pintype "passive"))
      (node (ref "S265_1") (pin "1") (pinfunction "1_1") (pintype "passive"))
    )
    (net (code "12") (name "/col12") (class "Default")
      (node (ref "S212") (pin "2") (pinfunction "2_2") (pintype "passive"))
      (node (ref "S212_1") (pin "2") (pinfunction "2_2") (pintype "passive"))
      (node (ref "S226") (pin "2") (pinfunction "2_2") (pintype "passive"))
      (node (ref "S240") (pin "2") (pinfunction "2_2") (pintype "passive"))
      (node (ref "S241") (pin "1") (pinfunction "1_1") (pintype "passive"))
      (node (ref "S254") (pin "2") (pinfunction "2_2") (pintype "passive"))
    )
    (net (code "13") (name "/col13") (class "Default")
      (node (ref "S213") (pin "2") (pinfunction "2_2") (pintype "passive"))
      (node (ref "S213_1") (pin "2") (pinfunction "2_2") (pintype "passive"))
      (node (ref "S227") (pin "2") (pinfunction "2_2") (pintype "passive"))
      (node (ref "S256") (pin "1") (pinfunction "1_1") (pintype "passive"))
      (node (ref "S256_1") (pin "1") (pinfunction "1_1") (pintype "passive"))
      (node (ref "S266") (pin "2") (pinfunction "2_2") (pintype "passive"))
      (node (ref "S266_1") (pin "2") (pinfunction "2_2") (pintype "passive"))
    )
    (net (code "14") (name "/col14") (class "Default")
      (node (ref "S214") (pin "2") (pinfunction "2_2") (pintype "passive"))
      (node (ref "S228") (pin "2") (pinfunction "2_2") (pintype "passive"))
      (node (ref "S242") (pin "2") (pinfunction "2_2") (pintype "passive"))
      (node (ref "S269") (pin "2") (pinfunction "2_2") (pintype "passive"))
      (node (ref "S300") (pin "2") (pinfunction "2_2") (pintype "passive"))
      (node (ref "S300_1") (pin "2") (pinfunction "2_2") (pintype "passive"))
      (node (ref "S300_2") (pin "2") (pinfunction "2_2") (pintype "passive"))
    )
    (net (code "15") (name "/row1") (class "Default")
      (node (ref "D201") (pin "2") (pinfunction "K_2") (pintype "passive"))
      (node (ref "D202") (pin "2") (pinfunction "K_2") (pintype "passive"))
      (node (ref "D203") (pin "2") (pinfunction "K_2") (pintype "passive"))
      (node (ref "D204") (pin "2") (pinfunction "K_2") (pintype "passive"))
      (node (ref "D205") (pin "2") (pinfunction "K_2") (pintype "passive"))
      (node (ref "D206") (pin "2") (pinfunction "K_2") (pintype "passive"))
      (node (ref "D207") (pin "2") (pinfunction "K_2") (pintype "passive"))
      (node (ref "D208") (pin "2") (pinfunction "K_2") (pintype "passive"))
      (node (ref "D209") (pin "2") (pinfunction "K_2") (pintype "passive"))
      (node (ref "D210") (pin "2") (pinfunction "K_2") (pintype "passive"))
      (node (ref "D211") (pin "2") (pinfunction "K_2") (pintype "passive"))
      (node (ref "D212") (pin "2") (pinfunction "K_2") (pintype "passive"))
      (node (ref "D213") (pin "2") (pinfunction "K_2") (pintype "passive"))
      (node (ref "D214") (pin "2") (pinfunction "K_2") (pintype "passive"))
    )
    (net (code "16") (name "/row2") (class "Default")
      (node (ref "D215") (pin "2") (pinfunction "K_2") (pintype "passive"))
      (node (ref "D216") (pin "2") (pinfunction "K_2") (pintype "passive"))
      (node (ref "D217") (pin "2") (pinfunction "K_2") (pintype "passive"))
      (node (ref "D218") (pin "2") (pinfunction "K_2") (pintype "passive"))
      (node (ref "D219") (pin "2") (pinfunction "K_2") (pintype "passive"))
      (node (ref "D220") (pin "2") (pinfunction "K_2") (pintype "passive"))
      (node (ref "D221") (pin "2") (pinfunction "K_2") (pintype "passive"))
      (node (ref "D222") (pin "2") (pinfunction "K_2") (pintype "passive"))
      (node (ref "D223") (pin "2") (pinfunction "K_2") (pintype "passive"))
      (node (ref "D224") (pin "2") (pinfunction "K_2") (pintype "passive"))
      (node (ref "D225") (pin "2") (pinfunction "K_2") (pintype "passive"))
      (node (ref "D226") (pin "2") (pinfunction "K_2") (pintype "passive"))
      (node (ref "D227") (pin "2") (pinfunction "K_2") (pintype "passive"))
      (node (ref "D228") (pin "2") (pinfunction "K_2") (pintype "passive"))
    )
    (net (code "17") (name "/row3") (class "Default")
      (node (ref "D229") (pin "2") (pinfunction "K_2") (pintype "passive"))
      (node (ref "D230") (pin "2") (pinfunction "K_2") (pintype "passive"))
      (node (ref "D231") (pin "2") (pinfunction "K_2") (pintype "passive"))
      (node (ref "D232") (pin "2") (pinfunction "K_2") (pintype "passive"))
      (node (ref "D233") (pin "2") (pinfunction "K_2") (pintype "passive"))
      (node (ref "D234") (pin "2") (pinfunction "K_2") (pintype "passive"))
      (node (ref "D235") (pin "2") (pinfunction "K_2") (pintype "passive"))
      (node (ref "D236") (pin "2") (pinfunction "K_2") (pintype "passive"))
      (node (ref "D237") (pin "2") (pinfunction "K_2") (pintype "passive"))
      (node (ref "D238") (pin "2") (pinfunction "K_2") (pintype "passive"))
      (node (ref "D239") (pin "2") (pinfunction "K_2") (pintype "passive"))
      (node (ref "D240") (pin "2") (pinfunction "K_2") (pintype "passive"))
      (node (ref "D300") (pin "2") (pinfunction "K_2") (pintype "passive"))
    )
    (net (code "18") (name "/row4") (class "Default")
      (node (ref "D242") (pin "2") (pinfunction "K_2") (pintype "passive"))
      (node (ref "D243") (pin "2") (pinfunction "K_2") (pintype "passive"))
      (node (ref "D244") (pin "2") (pinfunction "K_2") (pintype "passive"))
      (node (ref "D245") (pin "2") (pinfunction "K_2") (pintype "passive"))
      (node (ref "D246") (pin "2") (pinfunction "K_2") (pintype "passive"))
      (node (ref "D247") (pin "2") (pinfunction "K_2") (pintype "passive"))
      (node (ref "D248") (pin "2") (pinfunction "K_2") (pintype "passive"))
      (node (ref "D249") (pin "2") (pinfunction "K_2") (pintype "passive"))
      (node (ref "D250") (pin "2") (pinfunction "K_2") (pintype "passive"))
      (node (ref "D251") (pin "2") (pinfunction "K_2") (pintype "passive"))
      (node (ref "D252") (pin "2") (pinfunction "K_2") (pintype "passive"))
      (node (ref "D253") (pin "2") (pinfunction "K_2") (pintype "passive"))
      (node (ref "D254") (pin "2") (pinfunction "K_2") (pintype "passive"))
      (node (ref "D255") (pin "2") (pinfunction "K_2") (pintype "passive"))
    )
    (net (code "19") (name "/row5") (class "Default")
      (node (ref "D241") (pin "2") (pinfunction "K_2") (pintype "passive"))
      (node (ref "D256") (pin "2") (pinfunction "K_2") (pintype "passive"))
      (node (ref "D257") (pin "2") (pinfunction "K_2") (pintype "passive"))
      (node (ref "D258") (pin "2") (pinfunction "K_2") (pintype "passive"))
      (node (ref "D260") (pin "2") (pinfunction "K_2") (pintype "passive"))
      (node (ref "D261") (pin "2") (pinfunction "K_2") (pintype "passive"))
      (node (ref "D262") (pin "2") (pinfunction "K_2") (pintype "passive"))
      (node (ref "D263") (pin "2") (pinfunction "K_2") (pintype "passive"))
      (node (ref "D264") (pin "2") (pinfunction "K_2") (pintype "passive"))
      (node (ref "D265") (pin "2") (pinfunction "K_2") (pintype "passive"))
      (node (ref "D266") (pin "2") (pinfunction "K_2") (pintype "passive"))
    )
    (net (code "20") (name "Net-(D201-A)") (class "Default")
      (node (ref "D201") (pin "1") (pinfunction "A_1") (pintype "passive"))
      (node (ref "S201") (pin "1") (pinfunction "1_1") (pintype "passive"))
      (node (ref "S201_1") (pin "1") (pinfunction "1_1") (pintype "passive"))
    )
    (net (code "21") (name "Net-(D202-A)") (class "Default")
      (node (ref "D202") (pin "1") (pinfunction "A_1") (pintype "passive"))
      (node (ref "S202") (pin "1") (pinfunction "1_1") (pintype "passive"))
      (node (ref "S202_1") (pin "1") (pinfunction "1_1") (pintype "passive"))
    )
    (net (code "22") (name "Net-(D203-A)") (class "Default")
      (node (ref "D203") (pin "1") (pinfunction "A_1") (pintype "passive"))
      (node (ref "S203") (pin "1") (pinfunction "1_1") (pintype "passive"))
      (node (ref "S203_1") (pin "1") (pinfunction "1_1") (pintype "passive"))
    )
    (net (code "23") (name "Net-(D204-A)") (class "Default")
      (node (ref "D204") (pin "1") (pinfunction "A_1") (pintype "passive"))
      (node (ref "S204") (pin "1") (pinfunction "1_1") (pintype "passive"))
      (node (ref "S204_1") (pin "1") (pinfunction "1_1") (pintype "passive"))
    )
    (net (code "24") (name "Net-(D205-A)") (class "Default")
      (node (ref "D205") (pin "1") (pinfunction "A_1") (pintype "passive"))
      (node (ref "S205") (pin "1") (pinfunction "1_1") (pintype "passive"))
      (node (ref "S205_1") (pin "1") (pinfunction "1_1") (pintype "passive"))
    )
    (net (code "25") (name "Net-(D206-A)") (class "Default")
      (node (ref "D206") (pin "1") (pinfunction "A_1") (pintype "passive"))
      (node (ref "S206") (pin "1") (pinfunction "1_1") (pintype "passive"))
      (node (ref "S206_1") (pin "1") (pinfunction "1_1") (pintype "passive"))
    )
    (net (code "26") (name "Net-(D207-A)") (class "Default")
      (node (ref "D207") (pin "1") (pinfunction "A_1") (pintype "passive"))
      (node (ref "S207") (pin "1") (pinfunction "1_1") (pintype "passive"))
      (node (ref "S207_1") (pin "1") (pinfunction "1_1") (pintype "passive"))
    )
    (net (code "27") (name "Net-(D208-A)") (class "Default")
      (node (ref "D208") (pin "1") (pinfunction "A_1") (pintype "passive"))
      (node (ref "S208") (pin "1") (pinfunction "1_1") (pintype "passive"))
      (node (ref "S208_1") (pin "1") (pinfunction "1_1") (pintype "passive"))
    )
    (net (code "28") (name "Net-(D209-A)") (class "Default")
      (node (ref "D209") (pin "1") (pinfunction "A_1") (pintype "passive"))
      (node (ref "S209") (pin "1") (pinfunction "1_1") (pintype "passive"))
      (node (ref "S209_1") (pin "1") (pinfunction "1_1") (pintype "passive"))
    )
    (net (code "29") (name "Net-(D210-A)") (class "Default")
      (node (ref "D210") (pin "1") (pinfunction "A_1") (pintype "passive"))
      (node (ref "S210") (pin "1") (pinfunction "1_1") (pintype "passive"))
      (node (ref "S210_1") (pin "1") (pinfunction "1_1") (pintype "passive"))
    )
    (net (code "30") (name "Net-(D211-A)") (class "Default")
      (node (ref "D211") (pin "1") (pinfunction "A_1") (pintype "passive"))
      (node (ref "S211") (pin "1") (pinfunction "1_1") (pintype "passive"))
      (node (ref "S211_1") (pin "1") (pinfunction "1_1") (pintype "passive"))
    )
    (net (code "31") (name "Net-(D212-A)") (class "Default")
      (node (ref "D212") (pin "1") (pinfunction "A_1") (pintype "passive"))
      (node (ref "S212") (pin "1") (pinfunction "1_1") (pintype "passive"))
      (node (ref "S212_1") (pin "1") (pinfunction "1_1") (pintype "passive"))
    )
    (net (code "32") (name "Net-(D213-A)") (class "Default")
      (node (ref "D213") (pin "1") (pinfunction "A_1") (pintype "passive"))
      (node (ref "S213") (pin "1") (pinfunction "1_1") (pintype "passive"))
      (node (ref "S213_1") (pin "1") (pinfunction "1_1") (pintype "passive"))
    )
    (net (code "33") (name "Net-(D214-A)") (class "Default")
      (node (ref "D214") (pin "1") (pinfunction "A_1") (pintype "passive"))
      (node (ref "S214") (pin "1") (pinfunction "1_1") (pintype "passive"))
    )
    (net (code "34") (name "Net-(D215-A)") (class "Default")
      (node (ref "D215") (pin "1") (pinfunction "A_1") (pintype "passive"))
      (node (ref "S215") (pin "1") (pinfunction "1_1") (pintype "passive"))
    )
    (net (code "35") (name "Net-(D216-A)") (class "Default")
      (node (ref "D216") (pin "1") (pinfunction "A_1") (pintype "passive"))
      (node (ref "S216") (pin "1") (pinfunction "1_1") (pintype "passive"))
    )
    (net (code "36") (name "Net-(D217-A)") (class "Default")
      (node (ref "D217") (pin "1") (pinfunction "A_1") (pintype "passive"))
      (node (ref "S217") (pin "1") (pinfunction "1_1") (pintype "passive"))
    )
    (net (code "37") (name "Net-(D218-A)") (class "Default")
      (node (ref "D218") (pin "1") (pinfunction "A_1") (pintype "passive"))
      (node (ref "S218") (pin "1") (pinfunction "1_1") (pintype "passive"))
    )
    (net (code "38") (name "Net-(D219-A)") (class "Default")
      (node (ref "D219") (pin "1") (pinfunction "A_1") (pintype "passive"))
      (node (ref "S219") (pin "1") (pinfunction "1_1") (pintype "passive"))
    )
    (net (code "39") (name "Net-(D220-A)") (class "Default")
      (node (ref "D220") (pin "1") (pinfunction "A_1") (pintype "passive"))
      (node (ref "S220") (pin "1") (pinfunction "1_1") (pintype "passive"))
    )
    (net (code "40") (name "Net-(D221-A)") (class "Default")
      (node (ref "D221") (pin "1") (pinfunction "A_1") (pintype "passive"))
      (node (ref "S221") (pin "1") (pinfunction "1_1") (pintype "passive"))
    )
    (net (code "41") (name "Net-(D222-A)") (class "Default")
      (node (ref "D222") (pin "1") (pinfunction "A_1") (pintype "passive"))
      (node (ref "S222") (pin "1") (pinfunction "1_1") (pintype "passive"))
    )
    (net (code "42") (name "Net-(D223-A)") (class "Default")
      (node (ref "D223") (pin "1") (pinfunction "A_1") (pintype "passive"))
      (node (ref "S223") (pin "1") (pinfunction "1_1") (pintype "passive"))
    )
    (net (code "43") (name "Net-(D224-A)") (class "Default")
      (node (ref "D224") (pin "1") (pinfunction "A_1") (pintype "passive"))
      (node (ref "S224") (pin "1") (pinfunction "1_1") (pintype "passive"))
    )
    (net (code "44") (name "Net-(D225-A)") (class "Default")
      (node (ref "D225") (pin "1") (pinfunction "A_1") (pintype "passive"))
      (node (ref "S225") (pin "1") (pinfunction "1_1") (pintype "passive"))
    )
    (net (code "45") (name "Net-(D226-A)") (class "Default")
      (node (ref "D226") (pin "1") (pinfunction "A_1") (pintype "passive"))
      (node (ref "S226") (pin "1") (pinfunction "1_1") (pintype "passive"))
    )
    (net (code "46") (name "Net-(D227-A)") (class "Default")
      (node (ref "D227") (pin "1") (pinfunction "A_1") (pintype "passive"))
      (node (ref "S227") (pin "1") (pinfunction "1_1") (pintype "passive"))
    )
    (net (code "47") (name "Net-(D228-A)") (class "Default")
      (node (ref "D228") (pin "1") (pinfunction "A_1") (pintype "passive"))
      (node (ref "S228") (pin "1") (pinfunction "1_1") (pintype "passive"))
    )
    (net (code "48") (name "Net-(D229-A)") (class "Default")
      (node (ref "D229") (pin "1") (pinfunction "A_1") (pintype "passive"))
      (node (ref "S229") (pin "1") (pinfunction "1_1") (pintype "passive"))
    )
    (net (code "49") (name "Net-(D230-A)") (class "Default")
      (node (ref "D230") (pin "1") (pinfunction "A_1") (pintype "passive"))
      (node (ref "S230") (pin "1") (pinfunction "1_1") (pintype "passive"))
    )
    (net (code "50") (name "Net-(D231-A)") (class "Default")
      (node (ref "D231") (pin "1") (pinfunction "A_1") (pintype "passive"))
      (node (ref "S231") (pin "1") (pinfunction "1_1") (pintype "passive"))
    )
    (net (code "51") (name "Net-(D232-A)") (class "Default")
      (node (ref "D232") (pin "1") (pinfunction "A_1") (pintype "passive"))
      (node (ref "S232") (pin "1") (pinfunction "1_1") (pintype "passive"))
    )
    (net (code "52") (name "Net-(D233-A)") (class "Default")
      (node (ref "D233") (pin "1") (pinfunction "A_1") (pintype "passive"))
      (node (ref "S233") (pin "1") (pinfunction "1_1") (pintype "passive"))
    )
    (net (code "53") (name "Net-(D234-A)") (class "Default")
      (node (ref "D234") (pin "1") (pinfunction "A_1") (pintype "passive"))
      (node (ref "S234") (pin "1") (pinfunction "1_1") (pintype "passive"))
    )
    (net (code "54") (name "Net-(D235-A)") (class "Default")
      (node (ref "D235") (pin "1") (pinfunction "A_1") (pintype "passive"))
      (node (ref "S235") (pin "1") (pinfunction "1_1") (pintype "passive"))
    )
    (net (code "55") (name "Net-(D236-A)") (class "Default")
      (node (ref "D236") (pin "1") (pinfunction "A_1") (pintype "passive"))
      (node (ref "S236") (pin "1") (pinfunction "1_1") (pintype "passive"))
    )
    (net (code "56") (name "Net-(D237-A)") (class "Default")
      (node (ref "D237") (pin "1") (pinfunction "A_1") (pintype "passive"))
      (node (ref "S237") (pin "1") (pinfunction "1_1") (pintype "passive"))
    )
    (net (code "57") (name "Net-(D238-A)") (class "Default")
      (node (ref "D238") (pin "1") (pinfunction "A_1") (pintype "passive"))
      (node (ref "S238") (pin "1") (pinfunction "1_1") (pintype "passive"))
    )
    (net (code "58") (name "Net-(D239-A)") (class "Default")
      (node (ref "D239") (pin "1") (pinfunction "A_1") (pintype "passive"))
      (node (ref "S239") (pin "1") (pinfunction "1_1") (pintype "passive"))
    )
    (net (code "59") (name "Net-(D240-A)") (class "Default")
      (node (ref "D240") (pin "1") (pinfunction "A_1") (pintype "passive"))
      (node (ref "S240") (pin "1") (pinfunction "1_1") (pintype "passive"))
    )
    (net (code "60") (name "Net-(D241-A)") (class "Default")
      (node (ref "D241") (pin "1") (pinfunction "A_1") (pintype "passive"))
      (node (ref "S241") (pin "2") (pinfunction "2_2") (pintype "passive"))
    )
    (net (code "61") (name "Net-(D242-A)") (class "Default")
      (node (ref "D242") (pin "1") (pinfunction "A_1") (pintype "passive"))
      (node (ref "S242") (pin "1") (pinfunction "1_1") (pintype "passive"))
    )
    (net (code "62") (name "Net-(D243-A)") (class "Default")
      (node (ref "D243") (pin "1") (pinfunction "A_1") (pintype "passive"))
      (node (ref "S243") (pin "1") (pinfunction "1_1") (pintype "passive"))
    )
    (net (code "63") (name "Net-(D244-A)") (class "Default")
      (node (ref "D244") (pin "1") (pinfunction "A_1") (pintype "passive"))
      (node (ref "S244") (pin "2") (pinfunction "2_2") (pintype "passive"))
    )
    (net (code "64") (name "Net-(D245-A)") (class "Default")
      (node (ref "D245") (pin "1") (pinfunction "A_1") (pintype "passive"))
      (node (ref "S245") (pin "1") (pinfunction "1_1") (pintype "passive"))
    )
    (net (code "65") (name "Net-(D246-A)") (class "Default")
      (node (ref "D246") (pin "1") (pinfunction "A_1") (pintype "passive"))
      (node (ref "S246") (pin "1") (pinfunction "1_1") (pintype "passive"))
    )
    (net (code "66") (name "Net-(D247-A)") (class "Default")
      (node (ref "D247") (pin "1") (pinfunction "A_1") (pintype "passive"))
      (node (ref "S247") (pin "1") (pinfunction "1_1") (pintype "passive"))
    )
    (net (code "67") (name "Net-(D248-A)") (class "Default")
      (node (ref "D248") (pin "1") (pinfunction "A_1") (pintype "passive"))
      (node (ref "S248") (pin "1") (pinfunction "1_1") (pintype "passive"))
    )
    (net (code "68") (name "Net-(D249-A)") (class "Default")
      (node (ref "D249") (pin "1") (pinfunction "A_1") (pintype "passive"))
      (node (ref "S249") (pin "1") (pinfunction "1_1") (pintype "passive"))
    )
    (net (code "69") (name "Net-(D250-A)") (class "Default")
      (node (ref "D250") (pin "1") (pinfunction "A_1") (pintype "passive"))
      (node (ref "S250") (pin "1") (pinfunction "1_1") (pintype "passive"))
    )
    (net (code "70") (name "Net-(D251-A)") (class "Default")
      (node (ref "D251") (pin "1") (pinfunction "A_1") (pintype "passive"))
      (node (ref "S251") (pin "1") (pinfunction "1_1") (pintype "passive"))
    )
    (net (code "71") (name "Net-(D252-A)") (class "Default")
      (node (ref "D252") (pin "1") (pinfunction "A_1") (pintype "passive"))
      (node (ref "S252") (pin "1") (pinfunction "1_1") (pintype "passive"))
    )
    (net (code "72") (name "Net-(D253-A)") (class "Default")
      (node (ref "D253") (pin "1") (pinfunction "A_1") (pintype "passive"))
      (node (ref "S253") (pin "1") (pinfunction "1_1") (pintype "passive"))
    )
    (net (code "73") (name "Net-(D254-A)") (class "Default")
      (node (ref "D254") (pin "1") (pinfunction "A_1") (pintype "passive"))
      (node (ref "S254") (pin "1") (pinfunction "1_1") (pintype "passive"))
    )
    (net (code "74") (name "Net-(D255-A)") (class "Default")
      (node (ref "D255") (pin "1") (pinfunction "A_1") (pintype "passive"))
      (node (ref "S256") (pin "2") (pinfunction "2_2") (pintype "passive"))
      (node (ref "S256_1") (pin "2") (pinfunction "2_2") (pintype "passive"))
    )
    (net (code "75") (name "Net-(D256-A)") (class "Default")
      (node (ref "D256") (pin "1") (pinfunction "A_1") (pintype "passive"))
      (node (ref "S269") (pin "1") (pinfunction "1_1") (pintype "passive"))
    )
    (net (code "76") (name "Net-(D257-A)") (class "Default")
      (node (ref "D257") (pin "1") (pinfunction "A_1") (pintype "passive"))
      (node (ref "S257") (pin "2") (pinfunction "2_2") (pintype "passive"))
      (node (ref "S257_1") (pin "2") (pinfunction "2_2") (pintype "passive"))
      (node (ref "S257_2") (pin "2") (pinfunction "2_2") (pintype "passive"))
    )
    (net (code "77") (name "Net-(D258-A)") (class "Default")
      (node (ref "D258") (pin "1") (pinfunction "A_1") (pintype "passive"))
      (node (ref "S258") (pin "1") (pinfunction "1_1") (pintype "passive"))
    )
    (net (code "78") (name "Net-(D260-A)") (class "Default")
      (node (ref "D260") (pin "1") (pinfunction "A_1") (pintype "passive"))
      (node (ref "S260") (pin "1") (pinfunction "1_1") (pintype "passive"))
      (node (ref "S260_1") (pin "1") (pinfunction "1_1") (pintype "passive"))
      (node (ref "S260_2") (pin "1") (pinfunction "1_1") (pintype "passive"))
      (node (ref "S260_3") (pin "1") (pinfunction "1_1") (pintype "passive"))
    )
    (net (code "79") (name "Net-(D261-A)") (class "Default")
      (node (ref "D261") (pin "1") (pinfunction "A_1") (pintype "passive"))
      (node (ref "S261") (pin "1") (pinfunction "1_1") (pintype "passive"))
      (node (ref "S261_1") (pin "1") (pinfunction "1_1") (pintype "passive"))
      (node (ref "S261_2") (pin "1") (pinfunction "1_1") (pintype "passive"))
    )
    (net (code "80") (name "Net-(D262-A)") (class "Default")
      (node (ref "D262") (pin "1") (pinfunction "A_1") (pintype "passive"))
      (node (ref "S262") (pin "2") (pinfunction "2_2") (pintype "passive"))
      (node (ref "S262_1") (pin "2") (pinfunction "2_2") (pintype "passive"))
      (node (ref "S262_2") (pin "2") (pinfunction "2_2") (pintype "passive"))
      (node (ref "S262_3") (pin "2") (pinfunction "2_2") (pintype "passive"))
    )
    (net (code "81") (name "Net-(D263-A)") (class "Default")
      (node (ref "D263") (pin "1") (pinfunction "A_1") (pintype "passive"))
      (node (ref "S263") (pin "2") (pinfunction "2_2") (pintype "passive"))
    )
    (net (code "82") (name "Net-(D264-A)") (class "Default")
      (node (ref "D264") (pin "1") (pinfunction "A_1") (pintype "passive"))
      (node (ref "S264") (pin "1") (pinfunction "1_1") (pintype "passive"))
      (node (ref "S264_1") (pin "1") (pinfunction "1_1") (pintype "passive"))
    )
    (net (code "83") (name "Net-(D265-A)") (class "Default")
      (node (ref "D265") (pin "1") (pinfunction "A_1") (pintype "passive"))
      (node (ref "S265") (pin "2") (pinfunction "2_2") (pintype "passive"))
      (node (ref "S265_1") (pin "2") (pinfunction "2_2") (pintype "passive"))
    )
    (net (code "84") (name "Net-(D266-A)") (class "Default")
      (node (ref "D266") (pin "1") (pinfunction "A_1") (pintype "passive"))
      (node (ref "S266") (pin "1") (pinfunction "1_1") (pintype "passive"))
      (node (ref "S266_1") (pin "1") (pinfunction "1_1") (pintype "passive"))
    )
    (net (code "85") (name "Net-(D300-A)") (class "Default")
      (node (ref "D300") (pin "1") (pinfunction "A_1") (pintype "passive"))
      (node (ref "S300") (pin "1") (pinfunction "1_1") (pintype "passive"))
      (node (ref "S300_1") (pin "1") (pinfunction "1_1") (pintype "passive"))
      (node (ref "S300_2") (pin "1") (pinfunction "1_1") (pintype "passive"))
    )
  )
)
